# mapleSDuino-V0_9_004-eagle7.net
KiCad netlist of a schematic drawn in EAGLE
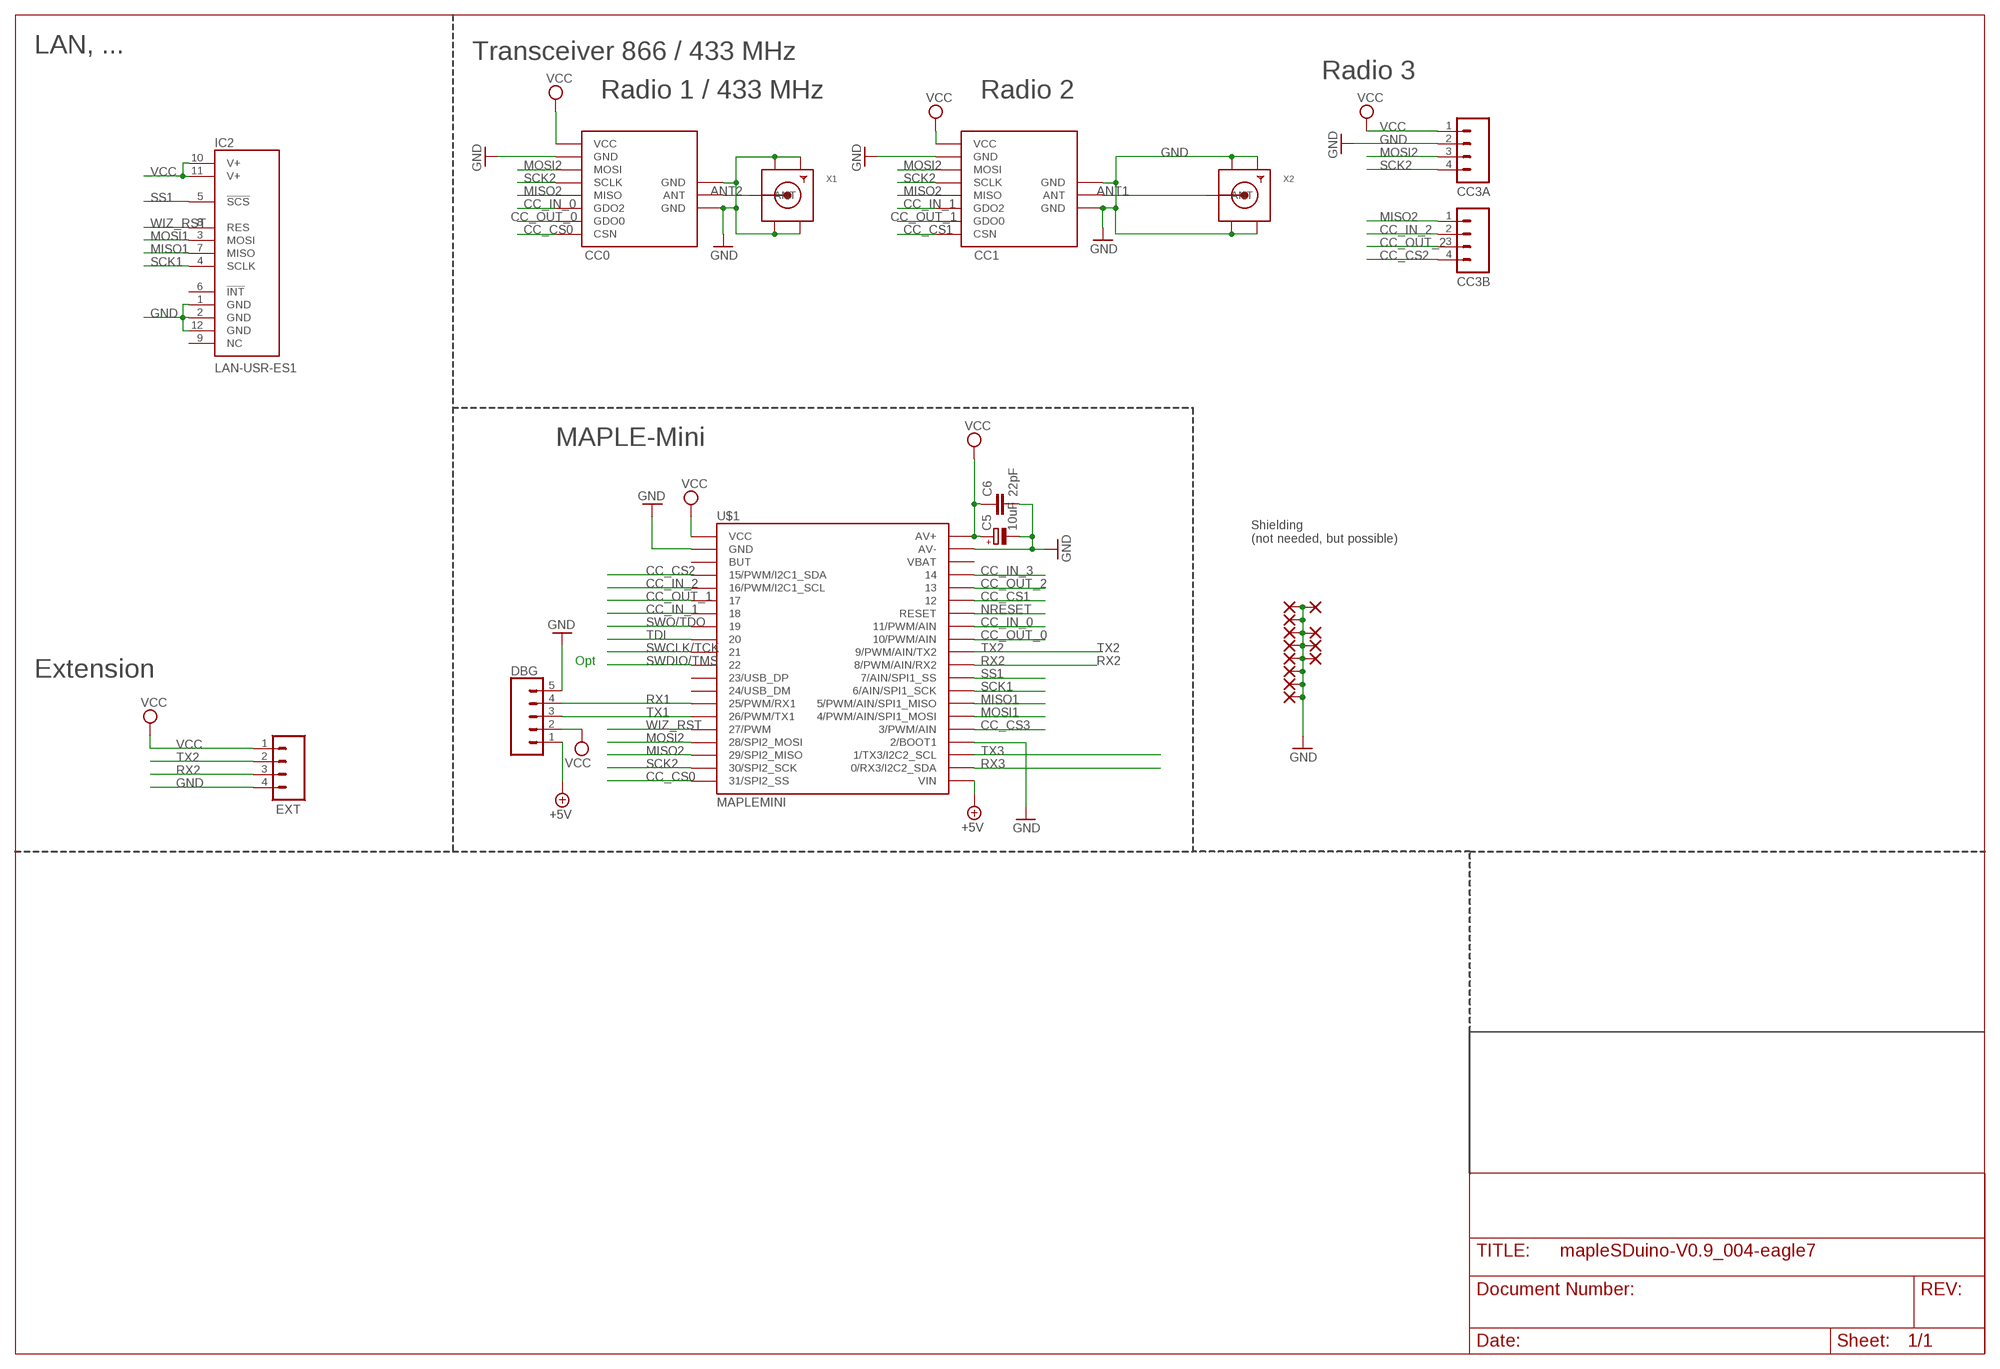
[diagram p0: schematic, sheet 1]

(export (version "E")
  (design (tool "Eeschema 10.0.6"))
  (components
    (comp (ref "C5")
      (value "10uF")
      (footprint "eagle-import:R_2012-12W")
      (libsource (lib "eagle-import") (part "CPOL-EUR/2012-12W"))
    )
    (comp (ref "C6")
      (value "22pF")
      (footprint "eagle-import:C0805")
      (libsource (lib "eagle-import") (part "C-EUC0805"))
    )
    (comp (ref "CC0")
      (value "CC1101")
      (footprint "eagle-import:CC1101_MODULE1_SMD")
      (libsource (lib "eagle-import") (part "CC1101_MODULE1SMALL"))
    )
    (comp (ref "CC1")
      (value "CC1101_MODULE1SMALL")
      (footprint "eagle-import:CC1101_MODULE1_SMD")
      (libsource (lib "eagle-import") (part "CC1101_MODULE1SMALL"))
    )
    (comp (ref "CC3A")
      (value "CONN_04PTH")
      (footprint "eagle-import:1X04")
      (libsource (lib "eagle-import") (part "CONN_04PTH"))
    )
    (comp (ref "CC3B")
      (value "CONN_04PTH")
      (footprint "eagle-import:1X04")
      (libsource (lib "eagle-import") (part "CONN_04PTH"))
    )
    (comp (ref "DBG")
      (value "CONN_05LOCK")
      (footprint "eagle-import:1X05_LOCK")
      (libsource (lib "eagle-import") (part "CONN_05LOCK"))
    )
    (comp (ref "EXT")
      (value "CONN_04PTH")
      (footprint "eagle-import:1X04")
      (libsource (lib "eagle-import") (part "CONN_04PTH"))
    )
    (comp (ref "IC2")
      (value "LAN-USR-ES1")
      (footprint "eagle-import:USR-ES1")
      (libsource (lib "eagle-import") (part "LAN-USR-ES1"))
    )
    (comp (ref "PAD1")
      (value "WIREPADSMD1,27-254")
      (footprint "eagle-import:SMD1,27-2,54")
      (libsource (lib "eagle-import") (part "WIREPADSMD1,27-254"))
    )
    (comp (ref "PAD2")
      (value "WIREPADSMD1,27-254")
      (footprint "eagle-import:SMD1,27-2,54")
      (libsource (lib "eagle-import") (part "WIREPADSMD1,27-254"))
    )
    (comp (ref "PAD3")
      (value "WIREPADSMD1,27-254")
      (footprint "eagle-import:SMD1,27-2,54")
      (libsource (lib "eagle-import") (part "WIREPADSMD1,27-254"))
    )
    (comp (ref "PAD4")
      (value "WIREPADSMD1,27-254")
      (footprint "eagle-import:SMD1,27-2,54")
      (libsource (lib "eagle-import") (part "WIREPADSMD1,27-254"))
    )
    (comp (ref "PAD5")
      (value "WIREPADSMD1,27-254")
      (footprint "eagle-import:SMD1,27-2,54")
      (libsource (lib "eagle-import") (part "WIREPADSMD1,27-254"))
    )
    (comp (ref "PAD6")
      (value "WIREPADSMD1,27-254")
      (footprint "eagle-import:SMD1,27-2,54")
      (libsource (lib "eagle-import") (part "WIREPADSMD1,27-254"))
    )
    (comp (ref "PAD7")
      (value "WIREPADSMD1,27-254")
      (footprint "eagle-import:SMD1,27-2,54")
      (libsource (lib "eagle-import") (part "WIREPADSMD1,27-254"))
    )
    (comp (ref "PAD8")
      (value "WIREPADSMD1,27-254")
      (footprint "eagle-import:SMD1,27-2,54")
      (libsource (lib "eagle-import") (part "WIREPADSMD1,27-254"))
    )
    (comp (ref "PAD9")
      (value "WIREPADSMD1,27-254")
      (footprint "eagle-import:SMD1,27-2,54")
      (libsource (lib "eagle-import") (part "WIREPADSMD1,27-254"))
    )
    (comp (ref "PAD10")
      (value "WIREPADSMD1,27-254")
      (footprint "eagle-import:SMD1,27-2,54")
      (libsource (lib "eagle-import") (part "WIREPADSMD1,27-254"))
    )
    (comp (ref "PAD11")
      (value "WIREPADSMD1,27-254")
      (footprint "eagle-import:SMD1,27-2,54")
      (libsource (lib "eagle-import") (part "WIREPADSMD1,27-254"))
    )
    (comp (ref "PAD12")
      (value "WIREPADSMD1,27-254")
      (footprint "eagle-import:SMD1,27-2,54")
      (libsource (lib "eagle-import") (part "WIREPADSMD1,27-254"))
    )
    (comp (ref "U$1")
      (value "MAPLEMINI")
      (footprint "eagle-import:20-DIP")
      (libsource (lib "eagle-import") (part "MAPLEMINI"))
    )
    (comp (ref "X1")
      (value "SMACONNECTOR_EDGE")
      (footprint "eagle-import:SMA_EDGELAUNCH")
      (libsource (lib "eagle-import") (part "SMACONNECTOR_EDGE"))
    )
    (comp (ref "X2")
      (value "SMACONNECTOR_EDGE")
      (footprint "eagle-import:SMA_EDGELAUNCH")
      (libsource (lib "eagle-import") (part "SMACONNECTOR_EDGE"))
    )
  )
  (nets
    (net (code "1") (name "+5V") (class "Default")
      (node (ref "DBG") (pin "1") (pinfunction "1_1") (pintype "passive"))
      (node (ref "U$1") (pin "21") (pinfunction "VIN_21") (pintype "bidirectional"))
    )
    (net (code "2") (name "/ANT1") (class "Default")
      (node (ref "CC1") (pin "ANT") (pinfunction "ANT_ANT") (pintype "output"))
      (node (ref "X2") (pin "P") (pinfunction "ANT_P") (pintype "bidirectional"))
    )
    (net (code "3") (name "/ANT2") (class "Default")
      (node (ref "CC0") (pin "ANT") (pinfunction "ANT_ANT") (pintype "output"))
      (node (ref "X1") (pin "P") (pinfunction "ANT_P") (pintype "bidirectional"))
    )
    (net (code "4") (name "/CC_CS0") (class "Default")
      (node (ref "CC0") (pin "CSN") (pinfunction "CSN_CSN") (pintype "bidirectional"))
      (node (ref "U$1") (pin "20") (pinfunction "31/SPI2_SS_20") (pintype "bidirectional"))
    )
    (net (code "5") (name "/CC_CS1") (class "Default")
      (node (ref "CC1") (pin "CSN") (pinfunction "CSN_CSN") (pintype "bidirectional"))
      (node (ref "U$1") (pin "35") (pinfunction "12_35") (pintype "bidirectional"))
    )
    (net (code "6") (name "/CC_CS2") (class "Default")
      (node (ref "CC3B") (pin "4") (pinfunction "4_4") (pintype "passive"))
      (node (ref "U$1") (pin "4") (pinfunction "15/PWM/I2C1_SDA_4") (pintype "bidirectional"))
    )
    (net (code "7") (name "/CC_CS3") (class "Default")
      (node (ref "U$1") (pin "25") (pinfunction "3/PWM/AIN_25") (pintype "bidirectional"))
    )
    (net (code "8") (name "/CC_IN_0") (class "Default")
      (node (ref "CC0") (pin "GDO2") (pinfunction "GDO2_GDO2") (pintype "bidirectional"))
      (node (ref "U$1") (pin "33") (pinfunction "11/PWM/AIN_33") (pintype "bidirectional"))
    )
    (net (code "9") (name "/CC_IN_1") (class "Default")
      (node (ref "CC1") (pin "GDO2") (pinfunction "GDO2_GDO2") (pintype "bidirectional"))
      (node (ref "U$1") (pin "7") (pinfunction "18_7") (pintype "bidirectional"))
    )
    (net (code "10") (name "/CC_IN_2") (class "Default")
      (node (ref "CC3B") (pin "2") (pinfunction "2_2") (pintype "passive"))
      (node (ref "U$1") (pin "5") (pinfunction "16/PWM/I2C1_SCL_5") (pintype "bidirectional"))
    )
    (net (code "11") (name "/CC_IN_3") (class "Default")
      (node (ref "U$1") (pin "37") (pinfunction "14_37") (pintype "bidirectional"))
    )
    (net (code "12") (name "/CC_OUT_0") (class "Default")
      (node (ref "CC0") (pin "GDO0") (pinfunction "GDO0_GDO0") (pintype "bidirectional"))
      (node (ref "U$1") (pin "32") (pinfunction "10/PWM/AIN_32") (pintype "bidirectional"))
    )
    (net (code "13") (name "/CC_OUT_1") (class "Default")
      (node (ref "CC1") (pin "GDO0") (pinfunction "GDO0_GDO0") (pintype "bidirectional"))
      (node (ref "U$1") (pin "6") (pinfunction "17_6") (pintype "bidirectional"))
    )
    (net (code "14") (name "/CC_OUT_2") (class "Default")
      (node (ref "CC3B") (pin "3") (pinfunction "3_3") (pintype "passive"))
      (node (ref "U$1") (pin "36") (pinfunction "13_36") (pintype "bidirectional"))
    )
    (net (code "15") (name "/MISO1") (class "Default")
      (node (ref "IC2") (pin "7") (pinfunction "MISO_7") (pintype "bidirectional"))
      (node (ref "U$1") (pin "27") (pinfunction "5/PWM/AIN/SPI1_MISO_27") (pintype "bidirectional"))
    )
    (net (code "16") (name "/MISO2") (class "Default")
      (node (ref "CC0") (pin "MISO") (pinfunction "MISO_MISO") (pintype "bidirectional"))
      (node (ref "CC1") (pin "MISO") (pinfunction "MISO_MISO") (pintype "bidirectional"))
      (node (ref "CC3B") (pin "1") (pinfunction "1_1") (pintype "passive"))
      (node (ref "U$1") (pin "18") (pinfunction "29/SPI2_MISO_18") (pintype "bidirectional"))
    )
    (net (code "17") (name "/MOSI1") (class "Default")
      (node (ref "IC2") (pin "3") (pinfunction "MOSI_3") (pintype "bidirectional"))
      (node (ref "U$1") (pin "26") (pinfunction "4/PWM/AIN/SPI1_MOSI_26") (pintype "bidirectional"))
    )
    (net (code "18") (name "/MOSI2") (class "Default")
      (node (ref "CC0") (pin "MOSI") (pinfunction "MOSI_MOSI") (pintype "bidirectional"))
      (node (ref "CC1") (pin "MOSI") (pinfunction "MOSI_MOSI") (pintype "bidirectional"))
      (node (ref "CC3A") (pin "3") (pinfunction "3_3") (pintype "passive"))
      (node (ref "U$1") (pin "17") (pinfunction "28/SPI2_MOSI_17") (pintype "bidirectional"))
    )
    (net (code "19") (name "/NRESET") (class "Default")
      (node (ref "U$1") (pin "34") (pinfunction "RESET_34") (pintype "bidirectional"))
    )
    (net (code "20") (name "/RX1") (class "Default")
      (node (ref "DBG") (pin "4") (pinfunction "4_4") (pintype "passive"))
      (node (ref "U$1") (pin "14") (pinfunction "25/PWM/RX1_14") (pintype "bidirectional"))
    )
    (net (code "21") (name "/RX2") (class "Default")
      (node (ref "EXT") (pin "3") (pinfunction "3_3") (pintype "passive"))
      (node (ref "U$1") (pin "30") (pinfunction "8/PWM/AIN/RX2_30") (pintype "bidirectional"))
    )
    (net (code "22") (name "/RX3") (class "Default")
      (node (ref "U$1") (pin "22") (pinfunction "0/RX3/I2C2_SDA_22") (pintype "bidirectional"))
    )
    (net (code "23") (name "/SCK1") (class "Default")
      (node (ref "IC2") (pin "4") (pinfunction "SCLK_4") (pintype "input"))
      (node (ref "U$1") (pin "28") (pinfunction "6/AIN/SPI1_SCK_28") (pintype "bidirectional"))
    )
    (net (code "24") (name "/SCK2") (class "Default")
      (node (ref "CC0") (pin "SCLK") (pinfunction "SCLK_SCLK") (pintype "bidirectional"))
      (node (ref "CC1") (pin "SCLK") (pinfunction "SCLK_SCLK") (pintype "bidirectional"))
      (node (ref "CC3A") (pin "4") (pinfunction "4_4") (pintype "passive"))
      (node (ref "U$1") (pin "19") (pinfunction "30/SPI2_SCK_19") (pintype "bidirectional"))
    )
    (net (code "25") (name "/SS1") (class "Default")
      (node (ref "IC2") (pin "5") (pinfunction "~{SCS}_5") (pintype "input"))
      (node (ref "U$1") (pin "29") (pinfunction "7/AIN/SPI1_SS_29") (pintype "bidirectional"))
    )
    (net (code "26") (name "/SWCLK{slash}TCK") (class "Default")
      (node (ref "U$1") (pin "10") (pinfunction "21_10") (pintype "bidirectional"))
    )
    (net (code "27") (name "/SWDIO{slash}TMS") (class "Default")
      (node (ref "U$1") (pin "11") (pinfunction "22_11") (pintype "bidirectional"))
    )
    (net (code "28") (name "/SWO{slash}TDO") (class "Default")
      (node (ref "U$1") (pin "8") (pinfunction "19_8") (pintype "bidirectional"))
    )
    (net (code "29") (name "/TDI") (class "Default")
      (node (ref "U$1") (pin "9") (pinfunction "20_9") (pintype "bidirectional"))
    )
    (net (code "30") (name "/TX1") (class "Default")
      (node (ref "DBG") (pin "3") (pinfunction "3_3") (pintype "passive"))
      (node (ref "U$1") (pin "15") (pinfunction "26/PWM/TX1_15") (pintype "bidirectional"))
    )
    (net (code "31") (name "/TX2") (class "Default")
      (node (ref "EXT") (pin "2") (pinfunction "2_2") (pintype "passive"))
      (node (ref "U$1") (pin "31") (pinfunction "9/PWM/AIN/TX2_31") (pintype "bidirectional"))
    )
    (net (code "32") (name "/TX3") (class "Default")
      (node (ref "U$1") (pin "23") (pinfunction "1/TX3/I2C2_SCL_23") (pintype "bidirectional"))
    )
    (net (code "33") (name "/WIZ_RST") (class "Default")
      (node (ref "IC2") (pin "8") (pinfunction "RES_8") (pintype "input"))
      (node (ref "U$1") (pin "16") (pinfunction "27/PWM_16") (pintype "bidirectional"))
    )
    (net (code "34") (name "GND") (class "Default")
      (node (ref "C5") (pin "-") (pinfunction "-_-") (pintype "passive"))
      (node (ref "C6") (pin "2") (pinfunction "2_2") (pintype "passive"))
      (node (ref "CC0") (pin "GND@0") (pinfunction "GND_GND@0") (pintype "power_in"))
      (node (ref "CC0") (pin "GND@1") (pinfunction "GND_GND@1") (pintype "power_in"))
      (node (ref "CC0") (pin "GND@2") (pinfunction "GND_GND@2") (pintype "power_in"))
      (node (ref "CC1") (pin "GND@0") (pinfunction "GND_GND@0") (pintype "power_in"))
      (node (ref "CC1") (pin "GND@1") (pinfunction "GND_GND@1") (pintype "power_in"))
      (node (ref "CC1") (pin "GND@2") (pinfunction "GND_GND@2") (pintype "power_in"))
      (node (ref "CC3A") (pin "2") (pinfunction "2_2") (pintype "passive"))
      (node (ref "DBG") (pin "5") (pinfunction "5_5") (pintype "passive"))
      (node (ref "EXT") (pin "4") (pinfunction "4_4") (pintype "passive"))
      (node (ref "IC2") (pin "1") (pinfunction "GND_1") (pintype "power_in"))
      (node (ref "IC2") (pin "12") (pinfunction "GND_12") (pintype "power_in"))
      (node (ref "IC2") (pin "2") (pinfunction "GND_2") (pintype "power_in"))
      (node (ref "PAD1") (pin "1") (pinfunction "P_1") (pintype "passive"))
      (node (ref "PAD10") (pin "1") (pinfunction "P_1") (pintype "passive"))
      (node (ref "PAD11") (pin "1") (pinfunction "P_1") (pintype "passive"))
      (node (ref "PAD12") (pin "1") (pinfunction "P_1") (pintype "passive"))
      (node (ref "PAD2") (pin "1") (pinfunction "P_1") (pintype "passive"))
      (node (ref "PAD3") (pin "1") (pinfunction "P_1") (pintype "passive"))
      (node (ref "PAD4") (pin "1") (pinfunction "P_1") (pintype "passive"))
      (node (ref "PAD5") (pin "1") (pinfunction "P_1") (pintype "passive"))
      (node (ref "PAD6") (pin "1") (pinfunction "P_1") (pintype "passive"))
      (node (ref "PAD7") (pin "1") (pinfunction "P_1") (pintype "passive"))
      (node (ref "PAD8") (pin "1") (pinfunction "P_1") (pintype "passive"))
      (node (ref "PAD9") (pin "1") (pinfunction "P_1") (pintype "passive"))
      (node (ref "U$1") (pin "2") (pinfunction "GND_2") (pintype "bidirectional"))
      (node (ref "U$1") (pin "24") (pinfunction "2/BOOT1_24") (pintype "bidirectional"))
      (node (ref "U$1") (pin "39") (pinfunction "AV-_39") (pintype "bidirectional"))
      (node (ref "X1") (pin "GND@1") (pinfunction "GND4_GND@1") (pintype "power_in"))
      (node (ref "X1") (pin "GND@2") (pinfunction "GND3_GND@2") (pintype "power_in"))
      (node (ref "X1") (pin "GND@3") (pinfunction "GND2_GND@3") (pintype "power_in"))
      (node (ref "X1") (pin "GND@4") (pinfunction "GND1_GND@4") (pintype "power_in"))
      (node (ref "X2") (pin "GND@1") (pinfunction "GND4_GND@1") (pintype "power_in"))
      (node (ref "X2") (pin "GND@2") (pinfunction "GND3_GND@2") (pintype "power_in"))
      (node (ref "X2") (pin "GND@3") (pinfunction "GND2_GND@3") (pintype "power_in"))
      (node (ref "X2") (pin "GND@4") (pinfunction "GND1_GND@4") (pintype "power_in"))
    )
    (net (code "35") (name "VCC") (class "Default")
      (node (ref "C5") (pin "+") (pinfunction "+_+") (pintype "passive"))
      (node (ref "C6") (pin "1") (pinfunction "1_1") (pintype "passive"))
      (node (ref "CC0") (pin "VCC") (pinfunction "VCC_VCC") (pintype "power_in"))
      (node (ref "CC1") (pin "VCC") (pinfunction "VCC_VCC") (pintype "power_in"))
      (node (ref "CC3A") (pin "1") (pinfunction "1_1") (pintype "passive"))
      (node (ref "DBG") (pin "2") (pinfunction "2_2") (pintype "passive"))
      (node (ref "EXT") (pin "1") (pinfunction "1_1") (pintype "passive"))
      (node (ref "IC2") (pin "10") (pinfunction "V+_10") (pintype "power_in"))
      (node (ref "IC2") (pin "11") (pinfunction "V+_11") (pintype "power_in"))
      (node (ref "U$1") (pin "1") (pinfunction "VCC_1") (pintype "bidirectional"))
      (node (ref "U$1") (pin "40") (pinfunction "AV+_40") (pintype "bidirectional"))
    )
    (net (code "36") (name "unconnected-(IC2-NC-Pad9)") (class "Default")
      (node (ref "IC2") (pin "9") (pinfunction "NC_9") (pintype "no_connect"))
    )
    (net (code "37") (name "unconnected-(IC2-~{INT}-Pad6)") (class "Default")
      (node (ref "IC2") (pin "6") (pinfunction "~{INT}_6") (pintype "output"))
    )
    (net (code "38") (name "unconnected-(U$1-23{slash}USB_DP-Pad12)") (class "Default")
      (node (ref "U$1") (pin "12") (pinfunction "23/USB_DP_12") (pintype "bidirectional"))
    )
    (net (code "39") (name "unconnected-(U$1-24{slash}USB_DM-Pad13)") (class "Default")
      (node (ref "U$1") (pin "13") (pinfunction "24/USB_DM_13") (pintype "bidirectional"))
    )
    (net (code "40") (name "unconnected-(U$1-BUT-Pad3)") (class "Default")
      (node (ref "U$1") (pin "3") (pinfunction "BUT_3") (pintype "bidirectional"))
    )
    (net (code "41") (name "unconnected-(U$1-VBAT-Pad38)") (class "Default")
      (node (ref "U$1") (pin "38") (pinfunction "VBAT_38") (pintype "bidirectional"))
    )
  )
)
